# QPL9547.net
KiCad netlist of a schematic drawn in Altium Designer
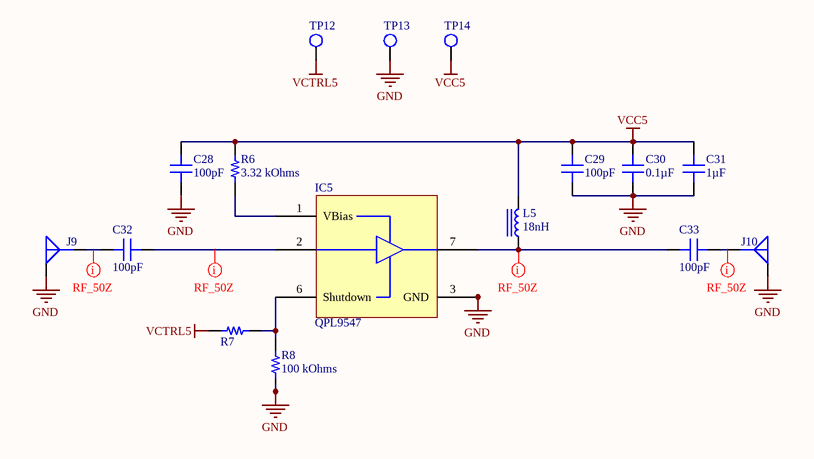
[diagram p0: QPL9547.SchDoc]

(export (version "E")
  (design (tool "Eeschema 10.0.6"))
  (components
    (comp (ref "C28")
      (value "100pF")
      (footprint "CAP 0402_1005")
      (description "CAP CER 100PF 50V C0G/NP0 0402")
      (fields
        (field (name "PART NUMBER") "GCM1555C1H101FA16D")
        (field (name "MANUFACTURER") "Murata Electronics")
      )
      (libsource (lib "Celestial Altium Library - altium_library") (part "Capacitor"))
    )
    (comp (ref "C29")
      (value "100pF")
      (footprint "CAP 0402_1005")
      (description "CAP CER 100PF 50V C0G/NP0 0402")
      (fields
        (field (name "PART NUMBER") "GCM1555C1H101FA16D")
        (field (name "MANUFACTURER") "Murata Electronics")
      )
      (libsource (lib "Celestial Altium Library - altium_library") (part "Capacitor"))
    )
    (comp (ref "C30")
      (value "0.1µF")
      (footprint "CAP 0402_1005")
      (description "CAP CER 0.1UF 16V X7R 0402")
      (fields (field (name "PART NUMBER") "EMK105B7104KV-F") (field (name "MANUFACTURER") "Taiyo Yuden"))
      (libsource (lib "Celestial Altium Library - altium_library") (part "Capacitor"))
    )
    (comp (ref "C31")
      (value "1µF")
      (footprint "CAP 0402_1005")
      (description "CAP CER 1UF 10V X5R 0402")
      (fields
        (field (name "PART NUMBER") "CL05A105KP5NNNC")
        (field (name "MANUFACTURER") "Samsung Electro-Mechanics")
      )
      (libsource (lib "Celestial Altium Library - altium_library") (part "Capacitor"))
    )
    (comp (ref "C32")
      (value "100pF")
      (footprint "CAP 0402_1005")
      (description "CAP CER 100PF 50V C0G/NP0 0402")
      (fields
        (field (name "PART NUMBER") "GCM1555C1H101FA16D")
        (field (name "MANUFACTURER") "Murata Electronics")
      )
      (libsource (lib "Celestial Altium Library - altium_library") (part "Capacitor"))
    )
    (comp (ref "C33")
      (value "100pF")
      (footprint "CAP 0402_1005")
      (description "CAP CER 100PF 50V C0G/NP0 0402")
      (fields
        (field (name "PART NUMBER") "GCM1555C1H101FA16D")
        (field (name "MANUFACTURER") "Murata Electronics")
      )
      (libsource (lib "Celestial Altium Library - altium_library") (part "Capacitor"))
    )
    (comp (ref "IC5")
      (value "QPL9547")
      (footprint "Qorvo LNA DFN-8 2X2")
      (description "0.1 -6 GHz Ultra Low-Noise LNA")
      (libsource (lib "IC") (part "QPL9547"))
    )
    (comp (ref "J9")
      (value "CON-SMA-EDGE-S")
      (footprint "CON-SMA-EDGE-S")
      (description "CONN SMA JACK STR EDGE MNT")
      (libsource (lib "Connector") (part "CON-SMA-EDGE-S"))
    )
    (comp (ref "J10")
      (value "CON-SMA-EDGE-S")
      (footprint "CON-SMA-EDGE-S")
      (description "CONN SMA JACK STR EDGE MNT")
      (libsource (lib "Connector") (part "CON-SMA-EDGE-S"))
    )
    (comp (ref "L5")
      (value "18nH")
      (footprint "0402CS")
      (description "Fixed Inductors 1005 18nH Unshld 5% 420mA 230mOhms AECQ2")
      (libsource (lib "Inductor") (part "0402CS-18NXJLW"))
    )
    (comp (ref "R6")
      (value "3.32 kOhms")
      (footprint "RES 0402_1005")
      (description "RES SMD 3.32K OHM 1% 1/16W 0402")
      (fields (field (name "PART NUMBER") "RC0402FR-073K32L") (field (name "MANUFACTURER") "Yageo"))
      (libsource (lib "Celestial Altium Library - altium_library") (part "Resistor"))
    )
    (comp (ref "R7")
      (value "~")
      (footprint "RES 0402_1005")
      (description "RES SMD 0 OHM JUMPER 1/16W 0402")
      (fields (field (name "PART NUMBER") "RC0402JR-070RP") (field (name "MANUFACTURER") "Yageo"))
      (libsource (lib "Celestial Altium Library - altium_library") (part "Resistor"))
    )
    (comp (ref "R8")
      (value "100 kOhms")
      (footprint "RES 0402_1005")
      (description "RES SMD 100K OHM 5% 1/10W 0402")
      (fields
        (field (name "PART NUMBER") "ERJ-2GEJ104X")
        (field (name "MANUFACTURER") "Panasonic Electronic Components")
      )
      (libsource (lib "Celestial Altium Library - altium_library") (part "Resistor"))
    )
    (comp (ref "TP12")
      (value "Test Point-THM")
      (footprint "KEYSTONE-THM-TestPoint")
      (description "THRU HOLE MOUNT TEST POINTS")
      (libsource (lib "Misc") (part "Test Point-THM"))
    )
    (comp (ref "TP13")
      (value "Test Point-THM")
      (footprint "KEYSTONE-THM-TestPoint")
      (description "THRU HOLE MOUNT TEST POINTS")
      (libsource (lib "Misc") (part "Test Point-THM"))
    )
    (comp (ref "TP14")
      (value "Test Point-THM")
      (footprint "KEYSTONE-THM-TestPoint")
      (description "THRU HOLE MOUNT TEST POINTS")
      (libsource (lib "Misc") (part "Test Point-THM"))
    )
  )
  (nets
    (net (code "1") (name "GND") (class "Default")
      (node (ref "C28") (pin "1") (pinfunction "1_1") (pintype "passive"))
      (node (ref "C29") (pin "1") (pinfunction "1_1") (pintype "passive"))
      (node (ref "C30") (pin "1") (pinfunction "1_1") (pintype "passive"))
      (node (ref "C31") (pin "1") (pinfunction "1_1") (pintype "passive"))
      (node (ref "IC5") (pin "3") (pinfunction "GND_3") (pintype "passive"))
      (node (ref "IC5") (pin "4") (pinfunction "GND_4") (pintype "passive"))
      (node (ref "IC5") (pin "5") (pinfunction "GND_5") (pintype "passive"))
      (node (ref "IC5") (pin "8") (pinfunction "GND_8") (pintype "passive"))
      (node (ref "IC5") (pin "9") (pinfunction "GND_9") (pintype "passive"))
      (node (ref "J10") (pin "2") (pinfunction "G_2") (pintype "passive"))
      (node (ref "J9") (pin "2") (pinfunction "G_2") (pintype "passive"))
      (node (ref "R8") (pin "1") (pinfunction "1_1") (pintype "passive"))
      (node (ref "TP13") (pin "1") (pinfunction "TP_1") (pintype "passive"))
    )
    (net (code "2") (name "Net-(IC5-IN)") (class "Default")
      (node (ref "C32") (pin "2") (pinfunction "2_2") (pintype "passive"))
      (node (ref "IC5") (pin "2") (pinfunction "IN_2") (pintype "passive"))
    )
    (net (code "3") (name "Net-(IC5-OUT)") (class "Default")
      (node (ref "C33") (pin "1") (pinfunction "1_1") (pintype "passive"))
      (node (ref "IC5") (pin "7") (pinfunction "OUT_7") (pintype "passive"))
      (node (ref "L5") (pin "1") (pinfunction "1_1") (pintype "passive"))
    )
    (net (code "4") (name "Net-(IC5-Shutdown)") (class "Default")
      (node (ref "IC5") (pin "6") (pinfunction "Shutdown_6") (pintype "passive"))
      (node (ref "R7") (pin "2") (pinfunction "2_2") (pintype "passive"))
      (node (ref "R8") (pin "2") (pinfunction "2_2") (pintype "passive"))
    )
    (net (code "5") (name "Net-(IC5-VBias)") (class "Default")
      (node (ref "IC5") (pin "1") (pinfunction "VBias_1") (pintype "passive"))
      (node (ref "R6") (pin "1") (pinfunction "1_1") (pintype "passive"))
    )
    (net (code "6") (name "Net-(J9-S)") (class "Default")
      (node (ref "C32") (pin "1") (pinfunction "1_1") (pintype "passive"))
      (node (ref "J9") (pin "1") (pinfunction "S_1") (pintype "passive"))
    )
    (net (code "7") (name "Net-(J10-S)") (class "Default")
      (node (ref "C33") (pin "2") (pinfunction "2_2") (pintype "passive"))
      (node (ref "J10") (pin "1") (pinfunction "S_1") (pintype "passive"))
    )
    (net (code "8") (name "VCC5") (class "Default")
      (node (ref "C28") (pin "2") (pinfunction "2_2") (pintype "passive"))
      (node (ref "C29") (pin "2") (pinfunction "2_2") (pintype "passive"))
      (node (ref "C30") (pin "2") (pinfunction "2_2") (pintype "passive"))
      (node (ref "C31") (pin "2") (pinfunction "2_2") (pintype "passive"))
      (node (ref "L5") (pin "2") (pinfunction "2_2") (pintype "passive"))
      (node (ref "R6") (pin "2") (pinfunction "2_2") (pintype "passive"))
      (node (ref "TP14") (pin "1") (pinfunction "TP_1") (pintype "passive"))
    )
    (net (code "9") (name "VCTRL5") (class "Default")
      (node (ref "R7") (pin "1") (pinfunction "1_1") (pintype "passive"))
      (node (ref "TP12") (pin "1") (pinfunction "TP_1") (pintype "passive"))
    )
  )
)
